# mmc_sd.net
KiCad netlist of a schematic drawn in Altium Designer
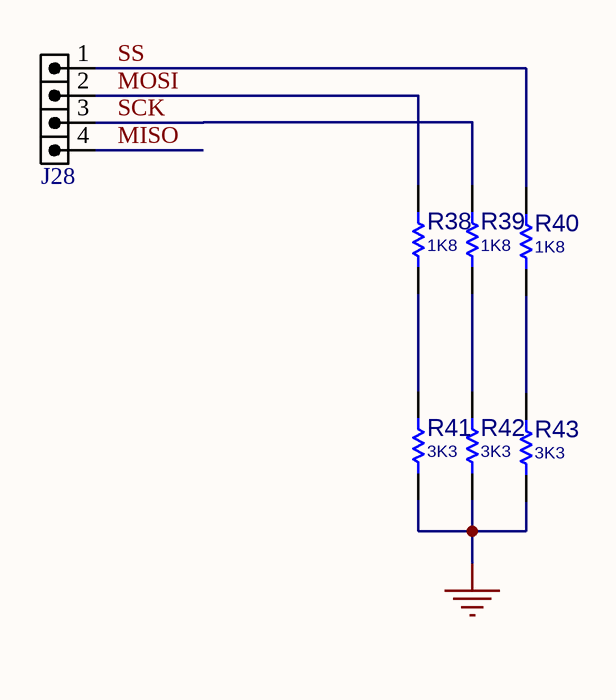
[diagram p0: mmc_sd.SchDoc]

(export (version "E")
  (design (tool "Eeschema 10.0.6"))
  (components
    (comp (ref "J28")
      (value "HDR1X4")
      (footprint "HDRMINI_M_1X4")
      (description "CONN, HEADER, Male, pitch: 1.27mm, 4POS")
      (libsource (lib "AvrDevelopmentBoard") (part "HDRMINI_M_1X4"))
    )
    (comp (ref "R38")
      (value "1K8")
      (footprint "R025W_AX04")
      (description "RESISTOR, THD")
      (fields (field (name "MANF_P#") "RK73H1ETTP4701F") (field (name "MANF") "KOA SPEER"))
      (libsource (lib "passive_thd") (part "RES_THD"))
    )
    (comp (ref "R39")
      (value "1K8")
      (footprint "R025W_AX04")
      (description "RESISTOR, THD")
      (fields (field (name "MANF_P#") "RK73H1ETTP4701F") (field (name "MANF") "KOA SPEER"))
      (libsource (lib "passive_thd") (part "RES_THD"))
    )
    (comp (ref "R40")
      (value "1K8")
      (footprint "R025W_AX04")
      (description "RESISTOR, THD")
      (fields (field (name "MANF_P#") "RK73H1ETTP4701F") (field (name "MANF") "KOA SPEER"))
      (libsource (lib "passive_thd") (part "RES_THD"))
    )
    (comp (ref "R41")
      (value "3K3")
      (footprint "R025W_AX04")
      (description "RESISTOR, THD")
      (fields (field (name "MANF_P#") "RK73H1ETTP4701F") (field (name "MANF") "KOA SPEER"))
      (libsource (lib "passive_thd") (part "RES_THD"))
    )
    (comp (ref "R42")
      (value "3K3")
      (footprint "R025W_AX04")
      (description "RESISTOR, THD")
      (fields (field (name "MANF_P#") "RK73H1ETTP4701F") (field (name "MANF") "KOA SPEER"))
      (libsource (lib "passive_thd") (part "RES_THD"))
    )
    (comp (ref "R43")
      (value "3K3")
      (footprint "R025W_AX04")
      (description "RESISTOR, THD")
      (fields (field (name "MANF_P#") "RK73H1ETTP4701F") (field (name "MANF") "KOA SPEER"))
      (libsource (lib "passive_thd") (part "RES_THD"))
    )
  )
  (nets
    (net (code "1") (name "/MISO") (class "Default")
      (node (ref "J28") (pin "4") (pinfunction "4_4") (pintype "passive"))
    )
    (net (code "2") (name "/MOSI") (class "Default")
      (node (ref "J28") (pin "2") (pinfunction "2_2") (pintype "passive"))
      (node (ref "R38") (pin "2") (pinfunction "2_2") (pintype "passive"))
    )
    (net (code "3") (name "/SCK") (class "Default")
      (node (ref "J28") (pin "3") (pinfunction "3_3") (pintype "passive"))
      (node (ref "R39") (pin "2") (pinfunction "2_2") (pintype "passive"))
    )
    (net (code "4") (name "/SS") (class "Default")
      (node (ref "J28") (pin "1") (pinfunction "1_1") (pintype "passive"))
      (node (ref "R40") (pin "2") (pinfunction "2_2") (pintype "passive"))
    )
    (net (code "5") (name "GND") (class "Default")
      (node (ref "R41") (pin "1") (pinfunction "1_1") (pintype "passive"))
      (node (ref "R42") (pin "1") (pinfunction "1_1") (pintype "passive"))
      (node (ref "R43") (pin "1") (pinfunction "1_1") (pintype "passive"))
    )
    (net (code "6") (name "Net-(R38-Pad1)") (class "Default")
      (node (ref "R38") (pin "1") (pinfunction "1_1") (pintype "passive"))
      (node (ref "R41") (pin "2") (pinfunction "2_2") (pintype "passive"))
    )
    (net (code "7") (name "Net-(R39-Pad1)") (class "Default")
      (node (ref "R39") (pin "1") (pinfunction "1_1") (pintype "passive"))
      (node (ref "R42") (pin "2") (pinfunction "2_2") (pintype "passive"))
    )
    (net (code "8") (name "Net-(R40-Pad1)") (class "Default")
      (node (ref "R40") (pin "1") (pinfunction "1_1") (pintype "passive"))
      (node (ref "R43") (pin "2") (pinfunction "2_2") (pintype "passive"))
    )
  )
)
